# tiny_drone_controller.net
KiCad netlist of a schematic drawn in EasyEDA
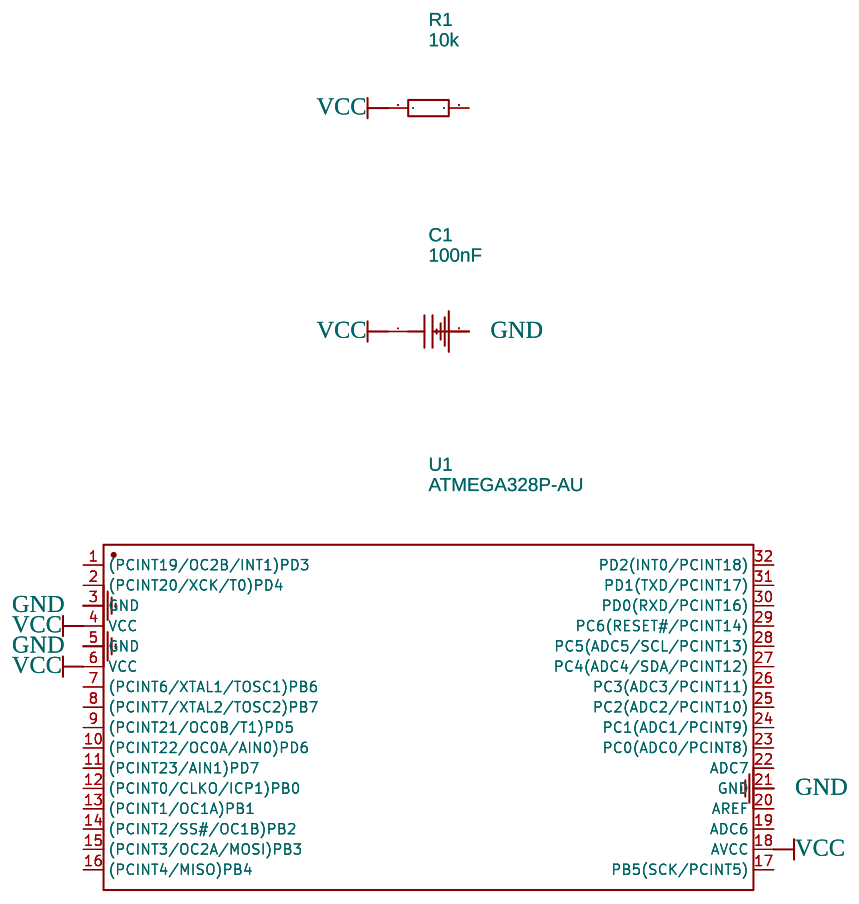
[diagram p0: schematic sheet]

(export (version "E")
  (design (tool "Eeschema 10.0.6"))
  (components
    (comp (ref "C1") (value "100nF") (libsource (lib "") (part "100nF")))
    (comp (ref "R1") (value "10k") (libsource (lib "") (part "10k")))
    (comp (ref "U1") (value "ATMEGA328P-AU") (libsource (lib "") (part "ATMEGA328P-AU")))
  )
  (nets
    (net (code "1") (name "GND") (class "Default")
      (node (ref "C1") (pin "2") (pinfunction "2_2") (pintype "unspecified"))
      (node (ref "U1") (pin "21") (pinfunction "GND_21") (pintype "unspecified"))
      (node (ref "U1") (pin "3") (pinfunction "GND_3") (pintype "unspecified"))
      (node (ref "U1") (pin "5") (pinfunction "GND_5") (pintype "unspecified"))
    )
    (net (code "2") (name "VCC") (class "Default")
      (node (ref "C1") (pin "1") (pinfunction "1_1") (pintype "unspecified"))
      (node (ref "R1") (pin "1") (pinfunction "1_1") (pintype "input"))
      (node (ref "U1") (pin "18") (pinfunction "AVCC_18") (pintype "unspecified"))
      (node (ref "U1") (pin "4") (pinfunction "VCC_4") (pintype "unspecified"))
      (node (ref "U1") (pin "6") (pinfunction "VCC_6") (pintype "unspecified"))
    )
    (net (code "3") (name "unconnected-(R1-Pad2)") (class "Default")
      (node (ref "R1") (pin "2") (pinfunction "2_2") (pintype "input"))
    )
    (net (code "4") (name "unconnected-(U1-(PCINT0{slash}CLKO{slash}ICP1)PB0-Pad12)") (class "Default")
      (node (ref "U1") (pin "12") (pinfunction "(PCINT0/CLKO/ICP1)PB0_12") (pintype "unspecified"))
    )
    (net (code "5") (name "unconnected-(U1-(PCINT1{slash}OC1A)PB1-Pad13)") (class "Default")
      (node (ref "U1") (pin "13") (pinfunction "(PCINT1/OC1A)PB1_13") (pintype "unspecified"))
    )
    (net (code "6") (name "unconnected-(U1-(PCINT2{slash}SS#{slash}OC1B)PB2-Pad14)") (class "Default")
      (node (ref "U1") (pin "14") (pinfunction "(PCINT2/SS#/OC1B)PB2_14") (pintype "unspecified"))
    )
    (net (code "7") (name "unconnected-(U1-(PCINT3{slash}OC2A{slash}MOSI)PB3-Pad15)") (class "Default")
      (node (ref "U1") (pin "15") (pinfunction "(PCINT3/OC2A/MOSI)PB3_15") (pintype "unspecified"))
    )
    (net (code "8") (name "unconnected-(U1-(PCINT4{slash}MISO)PB4-Pad16)") (class "Default")
      (node (ref "U1") (pin "16") (pinfunction "(PCINT4/MISO)PB4_16") (pintype "unspecified"))
    )
    (net (code "9") (name "unconnected-(U1-(PCINT6{slash}XTAL1{slash}TOSC1)PB6-Pad7)") (class "Default")
      (node (ref "U1") (pin "7") (pinfunction "(PCINT6/XTAL1/TOSC1)PB6_7") (pintype "unspecified"))
    )
    (net (code "10") (name "unconnected-(U1-(PCINT7{slash}XTAL2{slash}TOSC2)PB7-Pad8)") (class "Default")
      (node (ref "U1") (pin "8") (pinfunction "(PCINT7/XTAL2/TOSC2)PB7_8") (pintype "unspecified"))
    )
    (net (code "11") (name "unconnected-(U1-(PCINT19{slash}OC2B{slash}INT1)PD3-Pad1)") (class "Default")
      (node (ref "U1") (pin "1") (pinfunction "(PCINT19/OC2B/INT1)PD3_1") (pintype "unspecified"))
    )
    (net (code "12") (name "unconnected-(U1-(PCINT20{slash}XCK{slash}T0)PD4-Pad2)") (class "Default")
      (node (ref "U1") (pin "2") (pinfunction "(PCINT20/XCK/T0)PD4_2") (pintype "unspecified"))
    )
    (net (code "13") (name "unconnected-(U1-(PCINT21{slash}OC0B{slash}T1)PD5-Pad9)") (class "Default")
      (node (ref "U1") (pin "9") (pinfunction "(PCINT21/OC0B/T1)PD5_9") (pintype "unspecified"))
    )
    (net (code "14") (name "unconnected-(U1-(PCINT22{slash}OC0A{slash}AIN0)PD6-Pad10)") (class "Default")
      (node (ref "U1") (pin "10") (pinfunction "(PCINT22/OC0A/AIN0)PD6_10") (pintype "unspecified"))
    )
    (net (code "15") (name "unconnected-(U1-(PCINT23{slash}AIN1)PD7-Pad11)") (class "Default")
      (node (ref "U1") (pin "11") (pinfunction "(PCINT23/AIN1)PD7_11") (pintype "unspecified"))
    )
    (net (code "16") (name "unconnected-(U1-ADC6-Pad19)") (class "Default")
      (node (ref "U1") (pin "19") (pinfunction "ADC6_19") (pintype "unspecified"))
    )
    (net (code "17") (name "unconnected-(U1-ADC7-Pad22)") (class "Default")
      (node (ref "U1") (pin "22") (pinfunction "ADC7_22") (pintype "unspecified"))
    )
    (net (code "18") (name "unconnected-(U1-AREF-Pad20)") (class "Default")
      (node (ref "U1") (pin "20") (pinfunction "AREF_20") (pintype "unspecified"))
    )
    (net (code "19") (name "unconnected-(U1-PB5(SCK{slash}PCINT5)-Pad17)") (class "Default")
      (node (ref "U1") (pin "17") (pinfunction "PB5(SCK/PCINT5)_17") (pintype "unspecified"))
    )
    (net (code "20") (name "unconnected-(U1-PC0(ADC0{slash}PCINT8)-Pad23)") (class "Default")
      (node (ref "U1") (pin "23") (pinfunction "PC0(ADC0/PCINT8)_23") (pintype "unspecified"))
    )
    (net (code "21") (name "unconnected-(U1-PC1(ADC1{slash}PCINT9)-Pad24)") (class "Default")
      (node (ref "U1") (pin "24") (pinfunction "PC1(ADC1/PCINT9)_24") (pintype "unspecified"))
    )
    (net (code "22") (name "unconnected-(U1-PC2(ADC2{slash}PCINT10)-Pad25)") (class "Default")
      (node (ref "U1") (pin "25") (pinfunction "PC2(ADC2/PCINT10)_25") (pintype "unspecified"))
    )
    (net (code "23") (name "unconnected-(U1-PC3(ADC3{slash}PCINT11)-Pad26)") (class "Default")
      (node (ref "U1") (pin "26") (pinfunction "PC3(ADC3/PCINT11)_26") (pintype "unspecified"))
    )
    (net (code "24") (name "unconnected-(U1-PC4(ADC4{slash}SDA{slash}PCINT12)-Pad27)") (class "Default")
      (node (ref "U1") (pin "27") (pinfunction "PC4(ADC4/SDA/PCINT12)_27") (pintype "unspecified"))
    )
    (net (code "25") (name "unconnected-(U1-PC5(ADC5{slash}SCL{slash}PCINT13)-Pad28)") (class "Default")
      (node (ref "U1") (pin "28") (pinfunction "PC5(ADC5/SCL/PCINT13)_28") (pintype "unspecified"))
    )
    (net (code "26") (name "unconnected-(U1-PC6(RESET#{slash}PCINT14)-Pad29)") (class "Default")
      (node (ref "U1") (pin "29") (pinfunction "PC6(RESET#/PCINT14)_29") (pintype "unspecified"))
    )
    (net (code "27") (name "unconnected-(U1-PD0(RXD{slash}PCINT16)-Pad30)") (class "Default")
      (node (ref "U1") (pin "30") (pinfunction "PD0(RXD/PCINT16)_30") (pintype "unspecified"))
    )
    (net (code "28") (name "unconnected-(U1-PD1(TXD{slash}PCINT17)-Pad31)") (class "Default")
      (node (ref "U1") (pin "31") (pinfunction "PD1(TXD/PCINT17)_31") (pintype "unspecified"))
    )
    (net (code "29") (name "unconnected-(U1-PD2(INT0{slash}PCINT18)-Pad32)") (class "Default")
      (node (ref "U1") (pin "32") (pinfunction "PD2(INT0/PCINT18)_32") (pintype "unspecified"))
    )
  )
)
